# FarmControl.net
KiCad netlist of a schematic drawn in EAGLE
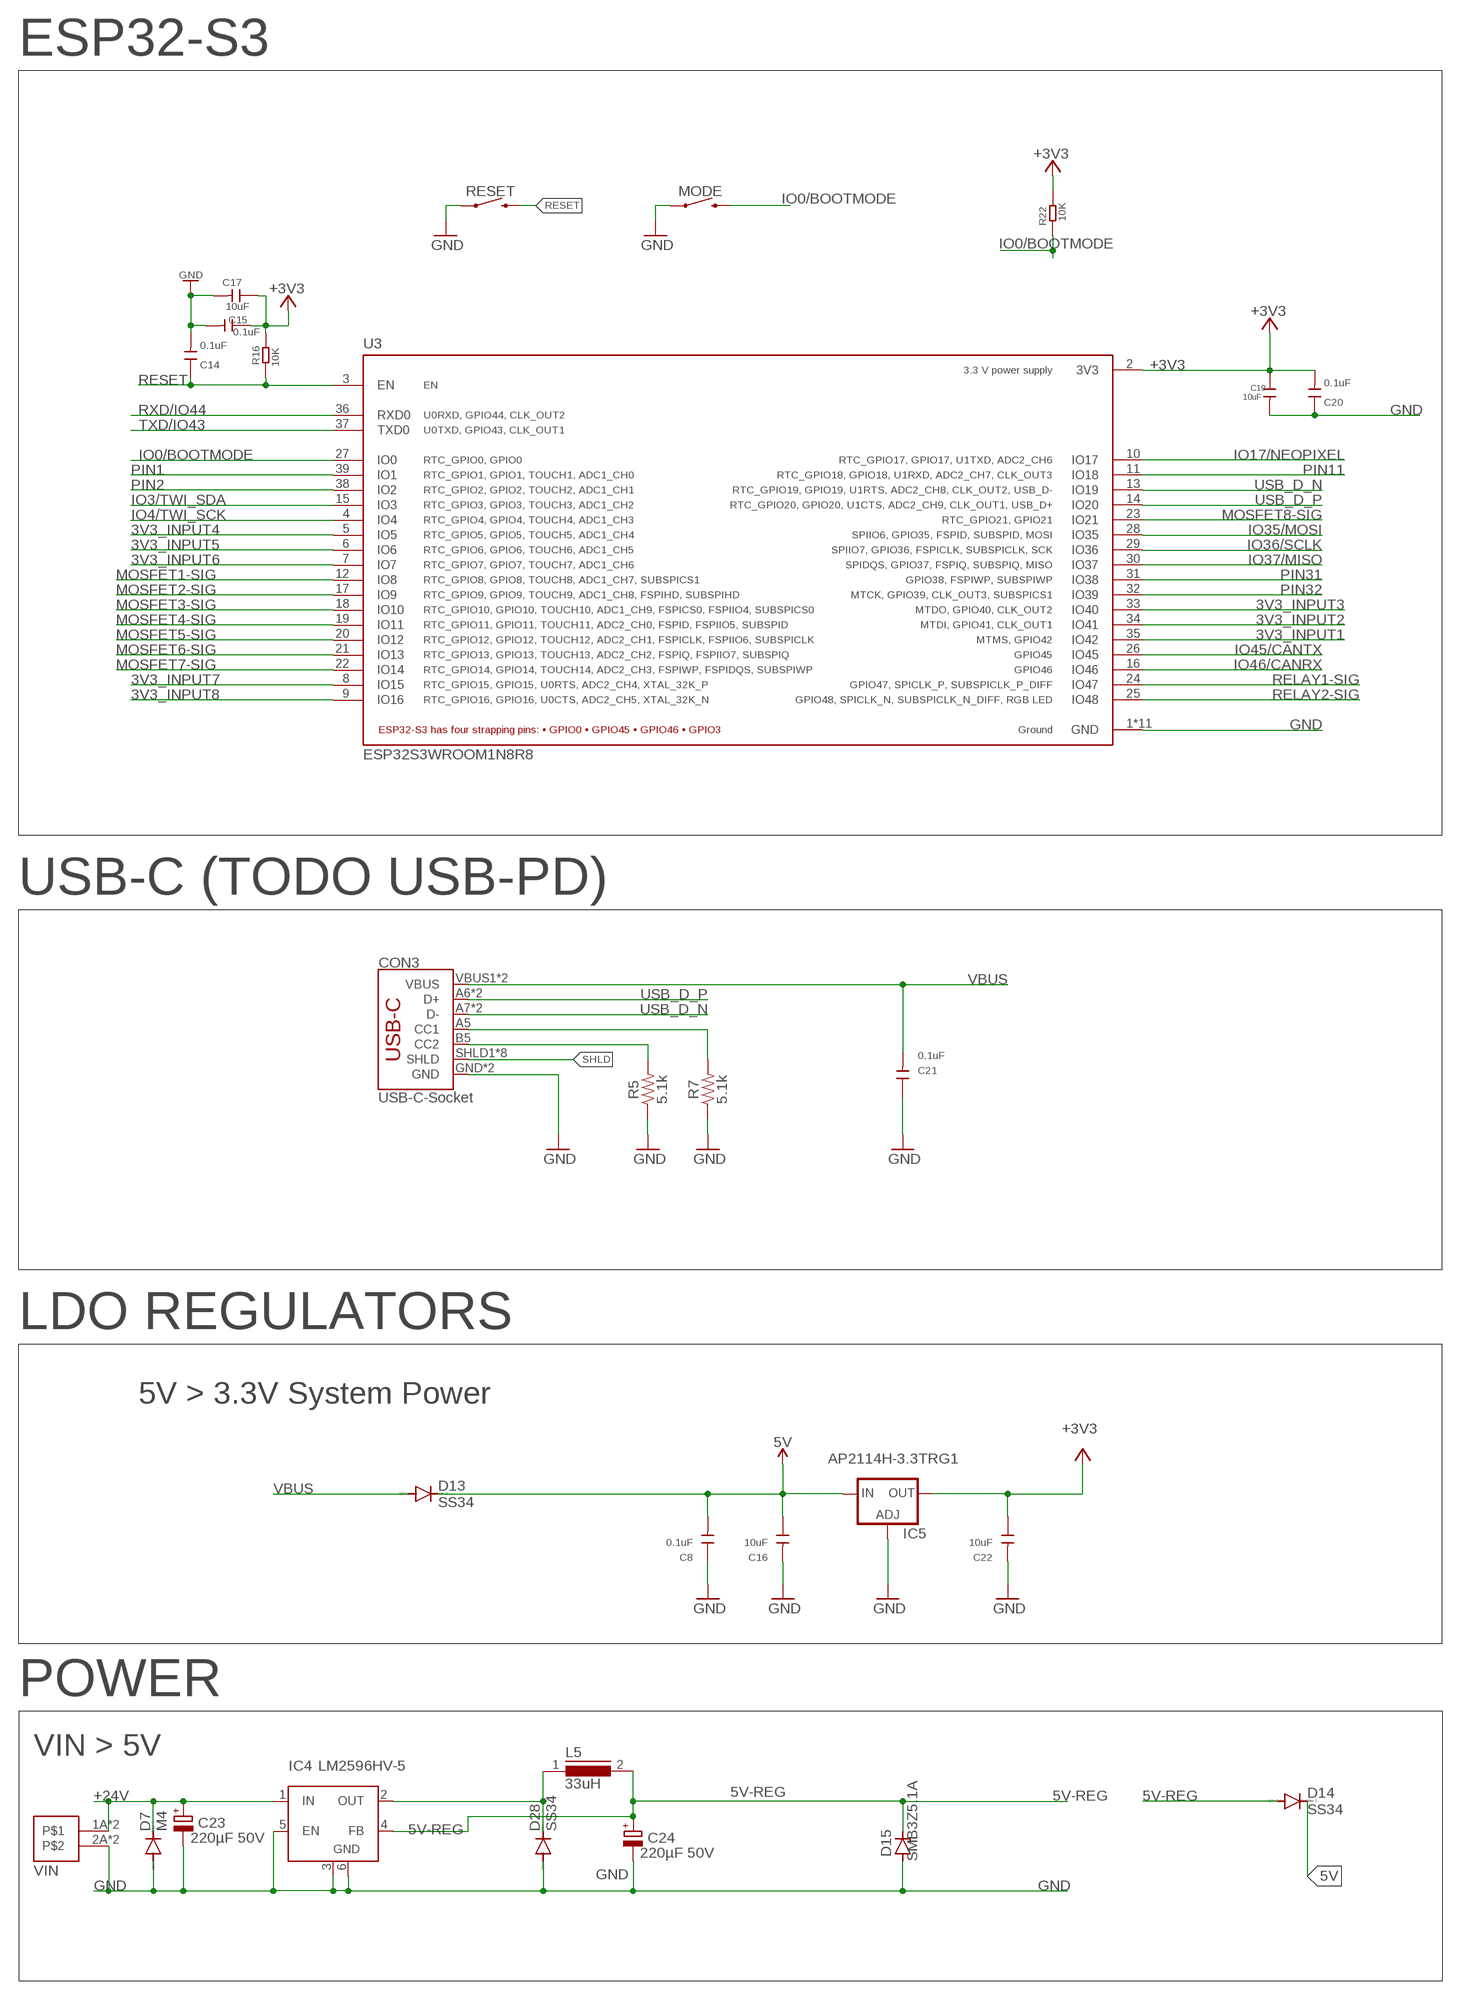
[diagram p0: schematic, sheet 1, part 1 of 3]
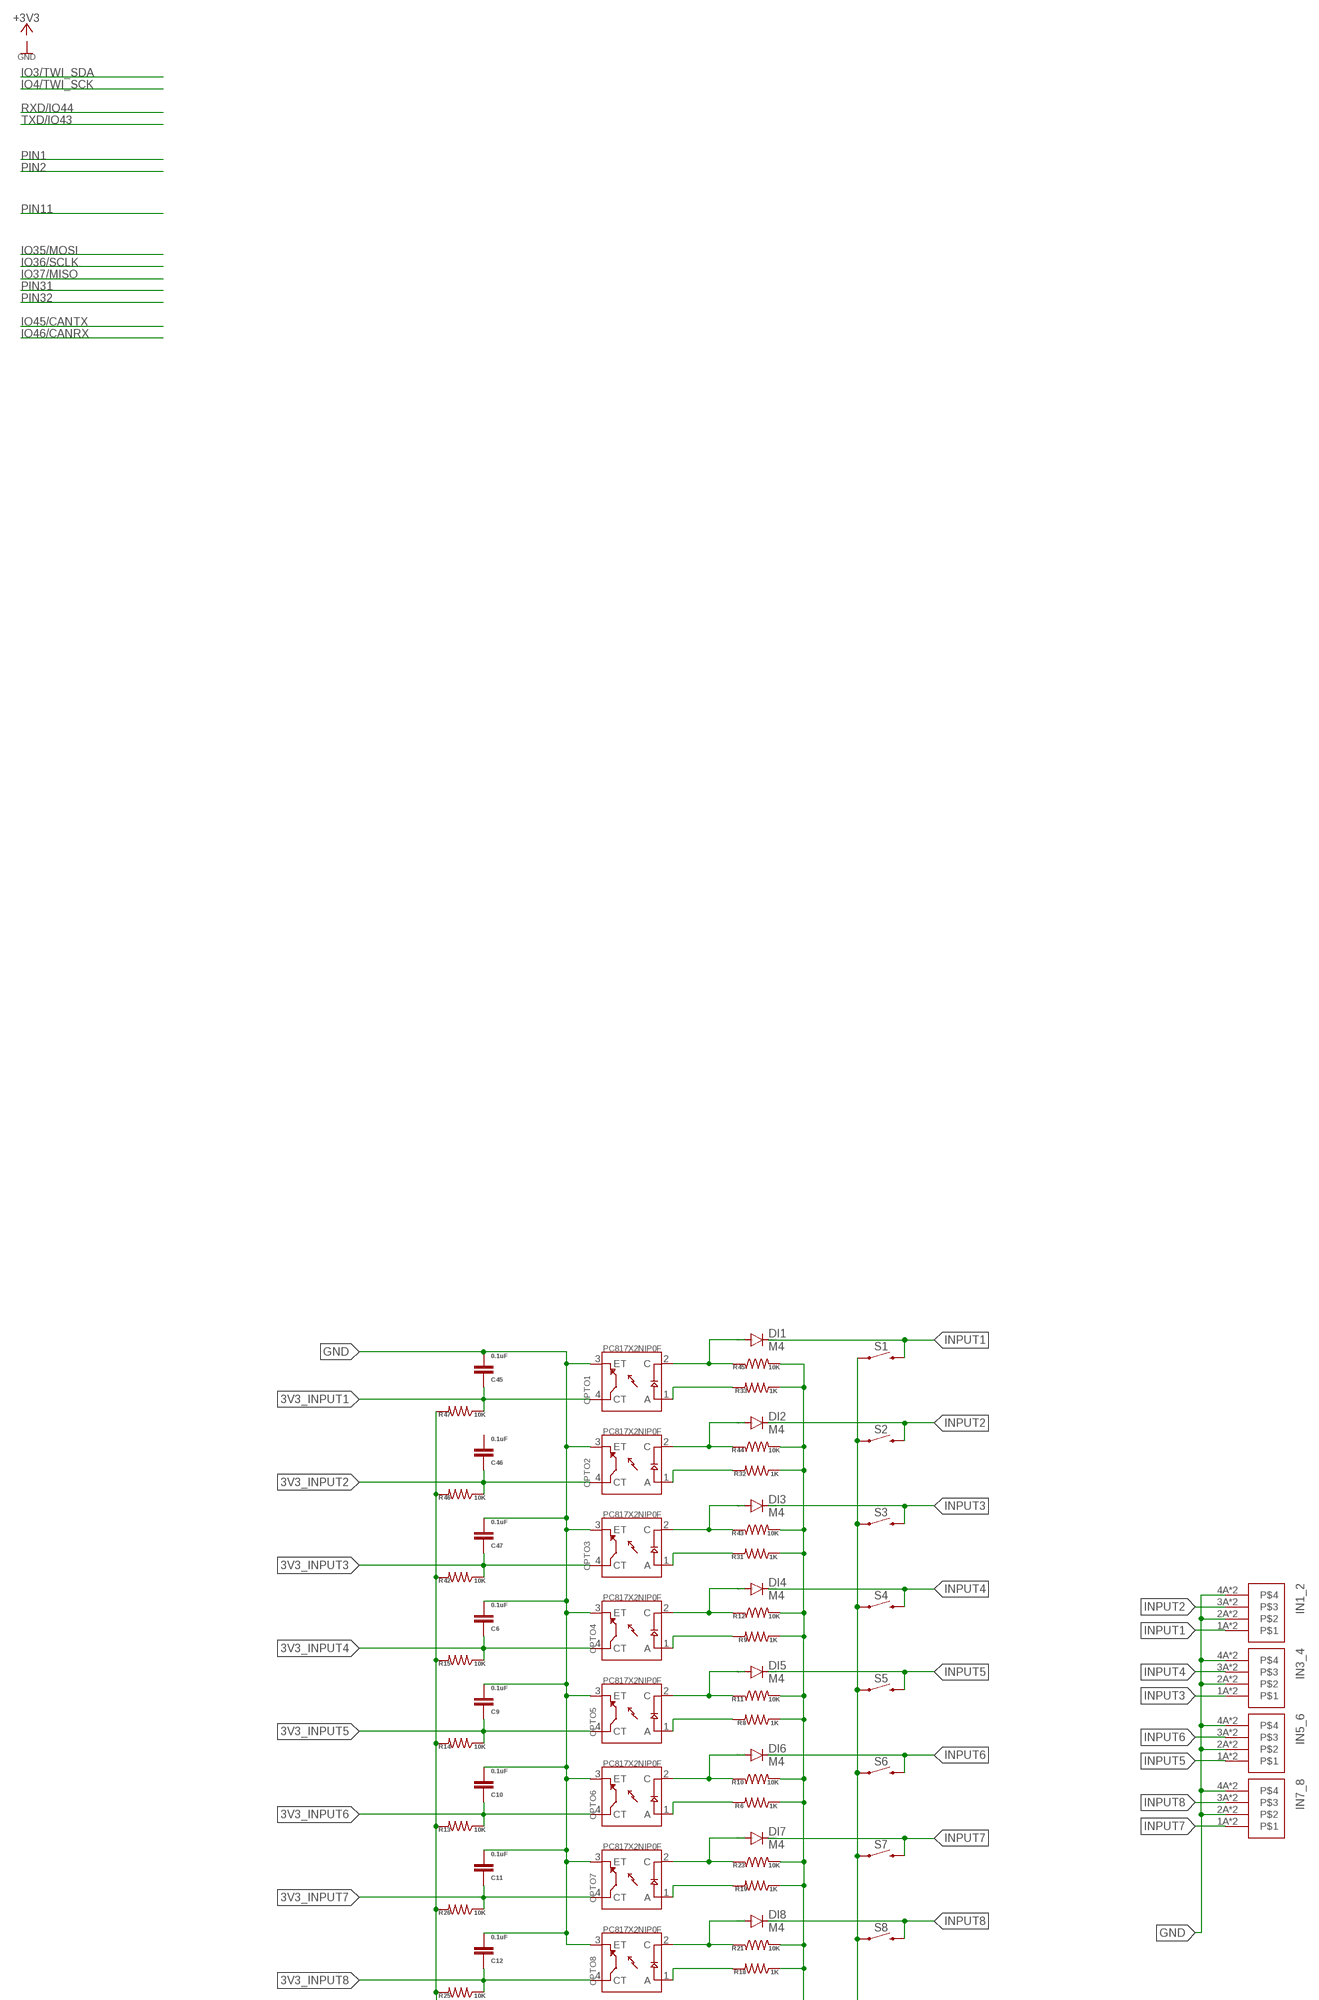
[diagram p1: schematic, sheet 1, part 2 of 3]
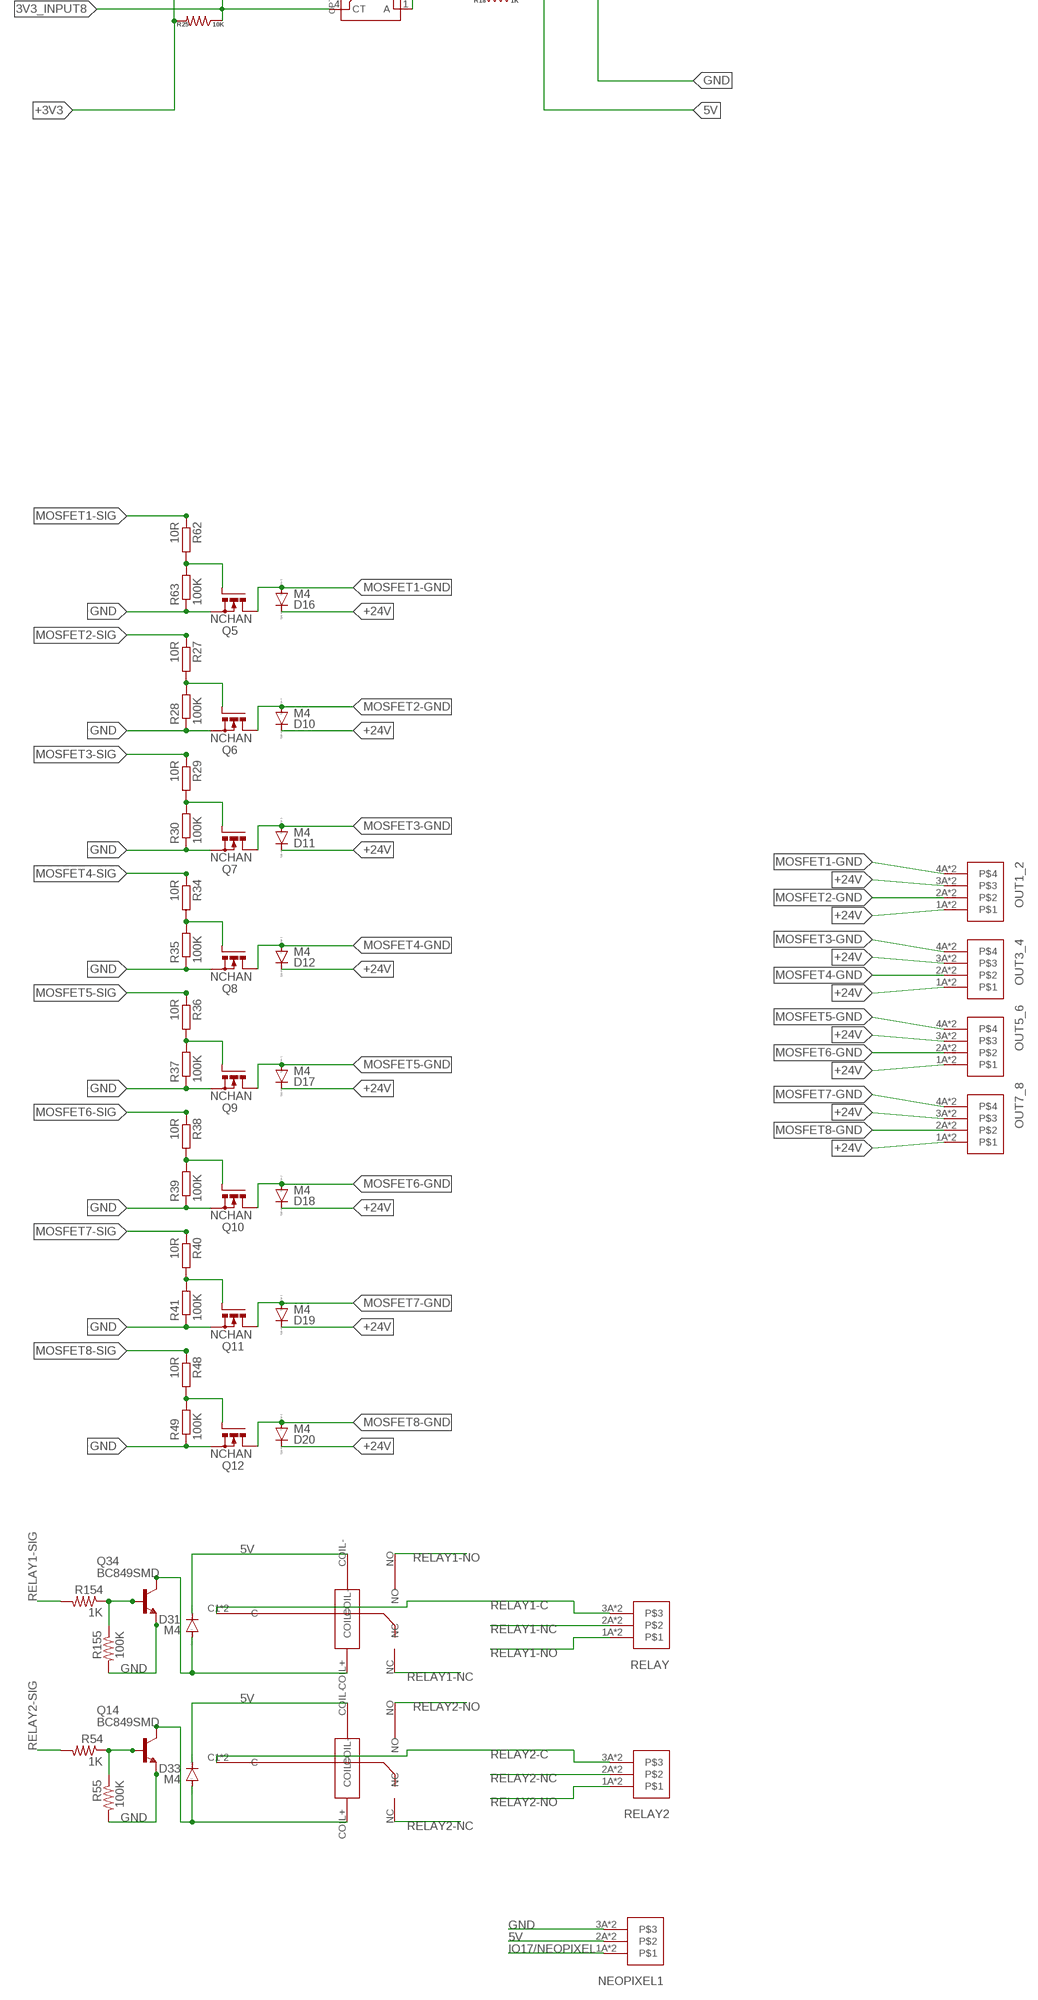
[diagram p2: schematic, sheet 1, part 3 of 3]

(export (version "E")
  (design (tool "Eeschema 10.0.6"))
  (components
    (comp (ref "C6")
      (value "0.1uF")
      (footprint "eagle-import:C1206")
      (libsource (lib "eagle-import") (part "C-EUC1206"))
    )
    (comp (ref "C8")
      (value "0.1uF")
      (footprint "eagle-import:DISCRETE_C1206")
      (libsource (lib "eagle-import") (part "DISCRETE_C-1206"))
    )
    (comp (ref "C9")
      (value "0.1uF")
      (footprint "eagle-import:C1206")
      (libsource (lib "eagle-import") (part "C-EUC1206"))
    )
    (comp (ref "C10")
      (value "0.1uF")
      (footprint "eagle-import:C1206")
      (libsource (lib "eagle-import") (part "C-EUC1206"))
    )
    (comp (ref "C11")
      (value "0.1uF")
      (footprint "eagle-import:C1206")
      (libsource (lib "eagle-import") (part "C-EUC1206"))
    )
    (comp (ref "C12")
      (value "0.1uF")
      (footprint "eagle-import:C1206")
      (libsource (lib "eagle-import") (part "C-EUC1206"))
    )
    (comp (ref "C14")
      (value "0.1uF")
      (footprint "eagle-import:DISCRETE_C1206")
      (libsource (lib "eagle-import") (part "DISCRETE_C-1206"))
    )
    (comp (ref "C15")
      (value "0.1uF")
      (footprint "eagle-import:DISCRETE_C1206")
      (libsource (lib "eagle-import") (part "DISCRETE_C-1206"))
    )
    (comp (ref "C16")
      (value "10uF")
      (footprint "eagle-import:C1206")
      (libsource (lib "eagle-import") (part "C-1206"))
    )
    (comp (ref "C17")
      (value "10uF")
      (footprint "eagle-import:DISCRETE_C1206")
      (libsource (lib "eagle-import") (part "DISCRETE_C-1206"))
    )
    (comp (ref "C19")
      (value "10uF")
      (footprint "eagle-import:C1206")
      (libsource (lib "eagle-import") (part "C-1206"))
    )
    (comp (ref "C20")
      (value "0.1uF")
      (footprint "eagle-import:DISCRETE_C1206")
      (libsource (lib "eagle-import") (part "DISCRETE_C-1206"))
    )
    (comp (ref "C21")
      (value "0.1uF")
      (footprint "eagle-import:DISCRETE_C1206")
      (libsource (lib "eagle-import") (part "DISCRETE_C-1206"))
    )
    (comp (ref "C22")
      (value "10uF")
      (footprint "eagle-import:C1206")
      (libsource (lib "eagle-import") (part "C-1206"))
    )
    (comp (ref "C23")
      (value "220µF 50V")
      (footprint "eagle-import:PANASONIC_E")
      (libsource (lib "eagle-import") (part "CPOL-EUE"))
    )
    (comp (ref "C24")
      (value "220µF 50V")
      (footprint "eagle-import:PANASONIC_E")
      (libsource (lib "eagle-import") (part "CPOL-EUE"))
    )
    (comp (ref "C45")
      (value "0.1uF")
      (footprint "eagle-import:C1206")
      (libsource (lib "eagle-import") (part "C-EUC1206"))
    )
    (comp (ref "C46")
      (value "0.1uF")
      (footprint "eagle-import:C1206")
      (libsource (lib "eagle-import") (part "C-EUC1206"))
    )
    (comp (ref "C47")
      (value "0.1uF")
      (footprint "eagle-import:C1206")
      (libsource (lib "eagle-import") (part "C-EUC1206"))
    )
    (comp (ref "CON3")
      (value "USB-C-Socket")
      (footprint "eagle-import:USB-C-16P")
      (libsource (lib "eagle-import") (part "USB_C16PIN"))
    )
    (comp (ref "D7")
      (value "M4")
      (footprint "eagle-import:DO-214AC")
      (libsource (lib "eagle-import") (part "DIODE-DO-214AC"))
    )
    (comp (ref "D10")
      (value "M4")
      (footprint "eagle-import:DO-214AC")
      (libsource (lib "eagle-import") (part "DIODE-DO-214AC"))
    )
    (comp (ref "D11")
      (value "M4")
      (footprint "eagle-import:DO-214AC")
      (libsource (lib "eagle-import") (part "DIODE-DO-214AC"))
    )
    (comp (ref "D12")
      (value "M4")
      (footprint "eagle-import:DO-214AC")
      (libsource (lib "eagle-import") (part "DIODE-DO-214AC"))
    )
    (comp (ref "D13")
      (value "SS34")
      (footprint "eagle-import:DO-214AC")
      (libsource (lib "eagle-import") (part "DIODE-DO-214AC"))
    )
    (comp (ref "D14")
      (value "SS34")
      (footprint "eagle-import:SMB")
      (libsource (lib "eagle-import") (part "DIODE-SMB"))
    )
    (comp (ref "D15")
      (value "SMB3Z5.1A")
      (footprint "eagle-import:SMB")
      (libsource (lib "eagle-import") (part "ZENER-DIODESMB"))
    )
    (comp (ref "D16")
      (value "M4")
      (footprint "eagle-import:DO-214AC")
      (libsource (lib "eagle-import") (part "DIODE-DO-214AC"))
    )
    (comp (ref "D17")
      (value "M4")
      (footprint "eagle-import:DO-214AC")
      (libsource (lib "eagle-import") (part "DIODE-DO-214AC"))
    )
    (comp (ref "D18")
      (value "M4")
      (footprint "eagle-import:DO-214AC")
      (libsource (lib "eagle-import") (part "DIODE-DO-214AC"))
    )
    (comp (ref "D19")
      (value "M4")
      (footprint "eagle-import:DO-214AC")
      (libsource (lib "eagle-import") (part "DIODE-DO-214AC"))
    )
    (comp (ref "D20")
      (value "M4")
      (footprint "eagle-import:DO-214AC")
      (libsource (lib "eagle-import") (part "DIODE-DO-214AC"))
    )
    (comp (ref "D28")
      (value "SS34")
      (footprint "eagle-import:SMB")
      (libsource (lib "eagle-import") (part "DIODE-SMB"))
    )
    (comp (ref "D31")
      (value "M4")
      (footprint "eagle-import:DO-214AC")
      (libsource (lib "eagle-import") (part "DIODE-DO-214AC"))
    )
    (comp (ref "D33")
      (value "M4")
      (footprint "eagle-import:DO-214AC")
      (libsource (lib "eagle-import") (part "DIODE-DO-214AC"))
    )
    (comp (ref "DI1")
      (value "M4")
      (footprint "eagle-import:DO-214AC")
      (libsource (lib "eagle-import") (part "DIODE-DO-214AC"))
    )
    (comp (ref "DI2")
      (value "M4")
      (footprint "eagle-import:DO-214AC")
      (libsource (lib "eagle-import") (part "DIODE-DO-214AC"))
    )
    (comp (ref "DI3")
      (value "M4")
      (footprint "eagle-import:DO-214AC")
      (libsource (lib "eagle-import") (part "DIODE-DO-214AC"))
    )
    (comp (ref "DI4")
      (value "M4")
      (footprint "eagle-import:DO-214AC")
      (libsource (lib "eagle-import") (part "DIODE-DO-214AC"))
    )
    (comp (ref "DI5")
      (value "M4")
      (footprint "eagle-import:DO-214AC")
      (libsource (lib "eagle-import") (part "DIODE-DO-214AC"))
    )
    (comp (ref "DI6")
      (value "M4")
      (footprint "eagle-import:DO-214AC")
      (libsource (lib "eagle-import") (part "DIODE-DO-214AC"))
    )
    (comp (ref "DI7")
      (value "M4")
      (footprint "eagle-import:DO-214AC")
      (libsource (lib "eagle-import") (part "DIODE-DO-214AC"))
    )
    (comp (ref "DI8")
      (value "M4")
      (footprint "eagle-import:DO-214AC")
      (libsource (lib "eagle-import") (part "DIODE-DO-214AC"))
    )
    (comp (ref "IC4")
      (value "LM2596HV-5")
      (footprint "eagle-import:TO263-5")
      (libsource (lib "eagle-import") (part "LM2596S"))
    )
    (comp (ref "IC5")
      (value "AP2114H-3.3TRG1")
      (footprint "eagle-import:SOT223")
      (libsource (lib "eagle-import") (part "LD117A?S33TR"))
    )
    (comp (ref "IN1_2")
      (value "WJ212R-THR-3.5-4")
      (footprint "eagle-import:WJ212R-THR-3.5-4")
      (libsource (lib "eagle-import") (part "WJ212R-THR-3.5-4"))
    )
    (comp (ref "IN3_4")
      (value "WJ212R-THR-3.5-4")
      (footprint "eagle-import:WJ212R-THR-3.5-4")
      (libsource (lib "eagle-import") (part "WJ212R-THR-3.5-4"))
    )
    (comp (ref "IN5_6")
      (value "WJ212R-THR-3.5-4")
      (footprint "eagle-import:WJ212R-THR-3.5-4")
      (libsource (lib "eagle-import") (part "WJ212R-THR-3.5-4"))
    )
    (comp (ref "IN7_8")
      (value "WJ212R-THR-3.5-4")
      (footprint "eagle-import:WJ212R-THR-3.5-4")
      (libsource (lib "eagle-import") (part "WJ212R-THR-3.5-4"))
    )
    (comp (ref "L5")
      (value "33uH")
      (footprint "eagle-import:DR127")
      (libsource (lib "eagle-import") (part "DR127"))
    )
    (comp (ref "MODE")
      (value "MOMENTARY-SWITCH-SPST-PTH-6.0MM")
      (footprint "eagle-import:TACTILE_SWITCH_PTH_6.0MM")
      (libsource (lib "eagle-import") (part "MOMENTARY-SWITCH-SPST-PTH-6.0MM"))
    )
    (comp (ref "NEOPIXEL1")
      (value "WJ212R-THR-3.5-3")
      (footprint "eagle-import:WJ212R-THR-3.5-3")
      (libsource (lib "eagle-import") (part "WJ212R-THR-3.5-3"))
    )
    (comp (ref "OPTO1")
      (value "PC817X2NIP0F")
      (footprint "eagle-import:SOT254P975X400-4N")
      (fields (field (name "MF") "Sharp Microelectronics"))
      (libsource (lib "eagle-import") (part "PC817X2NIP0F"))
    )
    (comp (ref "OPTO2")
      (value "PC817X2NIP0F")
      (footprint "eagle-import:SOT254P975X400-4N")
      (fields (field (name "MF") "Sharp Microelectronics"))
      (libsource (lib "eagle-import") (part "PC817X2NIP0F"))
    )
    (comp (ref "OPTO3")
      (value "PC817X2NIP0F")
      (footprint "eagle-import:SOT254P975X400-4N")
      (fields (field (name "MF") "Sharp Microelectronics"))
      (libsource (lib "eagle-import") (part "PC817X2NIP0F"))
    )
    (comp (ref "OPTO4")
      (value "PC817X2NIP0F")
      (footprint "eagle-import:SOT254P975X400-4N")
      (fields (field (name "MF") "Sharp Microelectronics"))
      (libsource (lib "eagle-import") (part "PC817X2NIP0F"))
    )
    (comp (ref "OPTO5")
      (value "PC817X2NIP0F")
      (footprint "eagle-import:SOT254P975X400-4N")
      (fields (field (name "MF") "Sharp Microelectronics"))
      (libsource (lib "eagle-import") (part "PC817X2NIP0F"))
    )
    (comp (ref "OPTO6")
      (value "PC817X2NIP0F")
      (footprint "eagle-import:SOT254P975X400-4N")
      (fields (field (name "MF") "Sharp Microelectronics"))
      (libsource (lib "eagle-import") (part "PC817X2NIP0F"))
    )
    (comp (ref "OPTO7")
      (value "PC817X2NIP0F")
      (footprint "eagle-import:SOT254P975X400-4N")
      (fields (field (name "MF") "Sharp Microelectronics"))
      (libsource (lib "eagle-import") (part "PC817X2NIP0F"))
    )
    (comp (ref "OPTO8")
      (value "PC817X2NIP0F")
      (footprint "eagle-import:SOT254P975X400-4N")
      (fields (field (name "MF") "Sharp Microelectronics"))
      (libsource (lib "eagle-import") (part "PC817X2NIP0F"))
    )
    (comp (ref "OUT1_2")
      (value "WJ212R-THR-3.5-4")
      (footprint "eagle-import:WJ212R-THR-3.5-4")
      (libsource (lib "eagle-import") (part "WJ212R-THR-3.5-4"))
    )
    (comp (ref "OUT3_4")
      (value "WJ212R-THR-3.5-4")
      (footprint "eagle-import:WJ212R-THR-3.5-4")
      (libsource (lib "eagle-import") (part "WJ212R-THR-3.5-4"))
    )
    (comp (ref "OUT5_6")
      (value "WJ212R-THR-3.5-4")
      (footprint "eagle-import:WJ212R-THR-3.5-4")
      (libsource (lib "eagle-import") (part "WJ212R-THR-3.5-4"))
    )
    (comp (ref "OUT7_8")
      (value "WJ212R-THR-3.5-4")
      (footprint "eagle-import:WJ212R-THR-3.5-4")
      (libsource (lib "eagle-import") (part "WJ212R-THR-3.5-4"))
    )
    (comp (ref "Q5")
      (value "NCHAN")
      (footprint "eagle-import:D-PAK_TO252AA")
      (libsource (lib "eagle-import") (part "N-POWER-MOSFETDPAK-MOSFET"))
    )
    (comp (ref "Q6")
      (value "NCHAN")
      (footprint "eagle-import:D-PAK_TO252AA")
      (libsource (lib "eagle-import") (part "N-POWER-MOSFETDPAK-MOSFET"))
    )
    (comp (ref "Q7")
      (value "NCHAN")
      (footprint "eagle-import:D-PAK_TO252AA")
      (libsource (lib "eagle-import") (part "N-POWER-MOSFETDPAK-MOSFET"))
    )
    (comp (ref "Q8")
      (value "NCHAN")
      (footprint "eagle-import:D-PAK_TO252AA")
      (libsource (lib "eagle-import") (part "N-POWER-MOSFETDPAK-MOSFET"))
    )
    (comp (ref "Q9")
      (value "NCHAN")
      (footprint "eagle-import:D-PAK_TO252AA")
      (libsource (lib "eagle-import") (part "N-POWER-MOSFETDPAK-MOSFET"))
    )
    (comp (ref "Q10")
      (value "NCHAN")
      (footprint "eagle-import:D-PAK_TO252AA")
      (libsource (lib "eagle-import") (part "N-POWER-MOSFETDPAK-MOSFET"))
    )
    (comp (ref "Q11")
      (value "NCHAN")
      (footprint "eagle-import:D-PAK_TO252AA")
      (libsource (lib "eagle-import") (part "N-POWER-MOSFETDPAK-MOSFET"))
    )
    (comp (ref "Q12")
      (value "NCHAN")
      (footprint "eagle-import:D-PAK_TO252AA")
      (libsource (lib "eagle-import") (part "N-POWER-MOSFETDPAK-MOSFET"))
    )
    (comp (ref "Q14")
      (value "BC849SMD")
      (footprint "eagle-import:SOT23-BEC")
      (libsource (lib "eagle-import") (part "BC849SMD"))
    )
    (comp (ref "Q34")
      (value "BC849SMD")
      (footprint "eagle-import:SOT23-BEC")
      (libsource (lib "eagle-import") (part "BC849SMD"))
    )
    (comp (ref "R5")
      (value "5.1k")
      (footprint "eagle-import:0603@1")
      (libsource (lib "eagle-import") (part "5.1KOHM5.1KOHM-0603-1/10W-1%"))
    )
    (comp (ref "R6")
      (value "1K")
      (footprint "eagle-import:R1206")
      (libsource (lib "eagle-import") (part "resistor_R-US_R1206"))
    )
    (comp (ref "R7")
      (value "5.1k")
      (footprint "eagle-import:0603@1")
      (libsource (lib "eagle-import") (part "5.1KOHM5.1KOHM-0603-1/10W-1%"))
    )
    (comp (ref "R8")
      (value "1K")
      (footprint "eagle-import:R1206")
      (libsource (lib "eagle-import") (part "resistor_R-US_R1206"))
    )
    (comp (ref "R9")
      (value "1K")
      (footprint "eagle-import:R1206")
      (libsource (lib "eagle-import") (part "resistor_R-US_R1206"))
    )
    (comp (ref "R10")
      (value "10K")
      (footprint "eagle-import:R1206")
      (libsource (lib "eagle-import") (part "resistor_R-US_R1206"))
    )
    (comp (ref "R11")
      (value "10K")
      (footprint "eagle-import:R1206")
      (libsource (lib "eagle-import") (part "resistor_R-US_R1206"))
    )
    (comp (ref "R12")
      (value "10K")
      (footprint "eagle-import:R1206")
      (libsource (lib "eagle-import") (part "resistor_R-US_R1206"))
    )
    (comp (ref "R13")
      (value "10K")
      (footprint "eagle-import:R1206")
      (libsource (lib "eagle-import") (part "resistor_R-US_R1206"))
    )
    (comp (ref "R14")
      (value "10K")
      (footprint "eagle-import:R1206")
      (libsource (lib "eagle-import") (part "resistor_R-US_R1206"))
    )
    (comp (ref "R15")
      (value "10K")
      (footprint "eagle-import:R1206")
      (libsource (lib "eagle-import") (part "resistor_R-US_R1206"))
    )
    (comp (ref "R16")
      (value "10K")
      (footprint "eagle-import:R1206")
      (libsource (lib "eagle-import") (part "R-1206"))
    )
    (comp (ref "R18")
      (value "1K")
      (footprint "eagle-import:R1206")
      (libsource (lib "eagle-import") (part "resistor_R-US_R1206"))
    )
    (comp (ref "R19")
      (value "1K")
      (footprint "eagle-import:R1206")
      (libsource (lib "eagle-import") (part "resistor_R-US_R1206"))
    )
    (comp (ref "R21")
      (value "10K")
      (footprint "eagle-import:R1206")
      (libsource (lib "eagle-import") (part "resistor_R-US_R1206"))
    )
    (comp (ref "R22")
      (value "10K")
      (footprint "eagle-import:R1206")
      (libsource (lib "eagle-import") (part "R-1206"))
    )
    (comp (ref "R23")
      (value "10K")
      (footprint "eagle-import:R1206")
      (libsource (lib "eagle-import") (part "resistor_R-US_R1206"))
    )
    (comp (ref "R25")
      (value "10K")
      (footprint "eagle-import:R1206")
      (libsource (lib "eagle-import") (part "resistor_R-US_R1206"))
    )
    (comp (ref "R26")
      (value "10K")
      (footprint "eagle-import:R1206")
      (libsource (lib "eagle-import") (part "resistor_R-US_R1206"))
    )
    (comp (ref "R27")
      (value "10R")
      (footprint "eagle-import:R1206")
      (libsource (lib "eagle-import") (part "R-EU_R1206"))
    )
    (comp (ref "R28")
      (value "100K")
      (footprint "eagle-import:R1206")
      (libsource (lib "eagle-import") (part "R-EU_R1206"))
    )
    (comp (ref "R29")
      (value "10R")
      (footprint "eagle-import:R1206")
      (libsource (lib "eagle-import") (part "R-EU_R1206"))
    )
    (comp (ref "R30")
      (value "100K")
      (footprint "eagle-import:R1206")
      (libsource (lib "eagle-import") (part "R-EU_R1206"))
    )
    (comp (ref "R31")
      (value "1K")
      (footprint "eagle-import:R1206")
      (libsource (lib "eagle-import") (part "resistor_R-US_R1206"))
    )
    (comp (ref "R32")
      (value "1K")
      (footprint "eagle-import:R1206")
      (libsource (lib "eagle-import") (part "resistor_R-US_R1206"))
    )
    (comp (ref "R33")
      (value "1K")
      (footprint "eagle-import:R1206")
      (libsource (lib "eagle-import") (part "resistor_R-US_R1206"))
    )
    (comp (ref "R34")
      (value "10R")
      (footprint "eagle-import:R1206")
      (libsource (lib "eagle-import") (part "R-EU_R1206"))
    )
    (comp (ref "R35")
      (value "100K")
      (footprint "eagle-import:R1206")
      (libsource (lib "eagle-import") (part "R-EU_R1206"))
    )
    (comp (ref "R36")
      (value "10R")
      (footprint "eagle-import:R1206")
      (libsource (lib "eagle-import") (part "R-EU_R1206"))
    )
    (comp (ref "R37")
      (value "100K")
      (footprint "eagle-import:R1206")
      (libsource (lib "eagle-import") (part "R-EU_R1206"))
    )
    (comp (ref "R38")
      (value "10R")
      (footprint "eagle-import:R1206")
      (libsource (lib "eagle-import") (part "R-EU_R1206"))
    )
    (comp (ref "R39")
      (value "100K")
      (footprint "eagle-import:R1206")
      (libsource (lib "eagle-import") (part "R-EU_R1206"))
    )
    (comp (ref "R40")
      (value "10R")
      (footprint "eagle-import:R1206")
      (libsource (lib "eagle-import") (part "R-EU_R1206"))
    )
    (comp (ref "R41")
      (value "100K")
      (footprint "eagle-import:R1206")
      (libsource (lib "eagle-import") (part "R-EU_R1206"))
    )
    (comp (ref "R42")
      (value "10K")
      (footprint "eagle-import:R1206")
      (libsource (lib "eagle-import") (part "resistor_R-US_R1206"))
    )
    (comp (ref "R43")
      (value "10K")
      (footprint "eagle-import:R1206")
      (libsource (lib "eagle-import") (part "resistor_R-US_R1206"))
    )
    (comp (ref "R44")
      (value "10K")
      (footprint "eagle-import:R1206")
      (libsource (lib "eagle-import") (part "resistor_R-US_R1206"))
    )
    (comp (ref "R45")
      (value "10K")
      (footprint "eagle-import:R1206")
      (libsource (lib "eagle-import") (part "resistor_R-US_R1206"))
    )
    (comp (ref "R46")
      (value "10K")
      (footprint "eagle-import:R1206")
      (libsource (lib "eagle-import") (part "resistor_R-US_R1206"))
    )
    (comp (ref "R47")
      (value "10K")
      (footprint "eagle-import:R1206")
      (libsource (lib "eagle-import") (part "resistor_R-US_R1206"))
    )
    (comp (ref "R48")
      (value "10R")
      (footprint "eagle-import:R1206")
      (libsource (lib "eagle-import") (part "R-EU_R1206"))
    )
    (comp (ref "R49")
      (value "100K")
      (footprint "eagle-import:R1206")
      (libsource (lib "eagle-import") (part "R-EU_R1206"))
    )
    (comp (ref "R54")
      (value "1K")
      (footprint "eagle-import:R1206")
      (libsource (lib "eagle-import") (part "R-US_R1206"))
    )
    (comp (ref "R55")
      (value "100K")
      (footprint "eagle-import:R1206")
      (libsource (lib "eagle-import") (part "R-US_R1206"))
    )
    (comp (ref "R62")
      (value "10R")
      (footprint "eagle-import:R1206")
      (libsource (lib "eagle-import") (part "R-EU_R1206"))
    )
    (comp (ref "R63")
      (value "100K")
      (footprint "eagle-import:R1206")
      (libsource (lib "eagle-import") (part "R-EU_R1206"))
    )
    (comp (ref "R154")
      (value "1K")
      (footprint "eagle-import:R1206")
      (libsource (lib "eagle-import") (part "R-US_R1206"))
    )
    (comp (ref "R155")
      (value "100K")
      (footprint "eagle-import:R1206")
      (libsource (lib "eagle-import") (part "R-US_R1206"))
    )
    (comp (ref "RELAY")
      (value "WJ212R-THR-3.5-3")
      (footprint "eagle-import:WJ212R-THR-3.5-3")
      (libsource (lib "eagle-import") (part "WJ212R-THR-3.5-3"))
    )
    (comp (ref "RELAY2")
      (value "WJ212R-THR-3.5-3")
      (footprint "eagle-import:WJ212R-THR-3.5-3")
      (libsource (lib "eagle-import") (part "WJ212R-THR-3.5-3"))
    )
    (comp (ref "RESET")
      (value "MOMENTARY-SWITCH-SPST-PTH-6.0MM")
      (footprint "eagle-import:TACTILE_SWITCH_PTH_6.0MM")
      (libsource (lib "eagle-import") (part "MOMENTARY-SWITCH-SPST-PTH-6.0MM"))
    )
    (comp (ref "S1")
      (value "MOMENTARY-SWITCH-SPST-PTH-6.0MM")
      (footprint "eagle-import:TACTILE_SWITCH_PTH_6.0MM")
      (libsource (lib "eagle-import") (part "MOMENTARY-SWITCH-SPST-PTH-6.0MM"))
    )
    (comp (ref "S2")
      (value "MOMENTARY-SWITCH-SPST-PTH-6.0MM")
      (footprint "eagle-import:TACTILE_SWITCH_PTH_6.0MM")
      (libsource (lib "eagle-import") (part "MOMENTARY-SWITCH-SPST-PTH-6.0MM"))
    )
    (comp (ref "S3")
      (value "MOMENTARY-SWITCH-SPST-PTH-6.0MM")
      (footprint "eagle-import:TACTILE_SWITCH_PTH_6.0MM")
      (libsource (lib "eagle-import") (part "MOMENTARY-SWITCH-SPST-PTH-6.0MM"))
    )
    (comp (ref "S4")
      (value "MOMENTARY-SWITCH-SPST-PTH-6.0MM")
      (footprint "eagle-import:TACTILE_SWITCH_PTH_6.0MM")
      (libsource (lib "eagle-import") (part "MOMENTARY-SWITCH-SPST-PTH-6.0MM"))
    )
    (comp (ref "S5")
      (value "MOMENTARY-SWITCH-SPST-PTH-6.0MM")
      (footprint "eagle-import:TACTILE_SWITCH_PTH_6.0MM")
      (libsource (lib "eagle-import") (part "MOMENTARY-SWITCH-SPST-PTH-6.0MM"))
    )
    (comp (ref "S6")
      (value "MOMENTARY-SWITCH-SPST-PTH-6.0MM")
      (footprint "eagle-import:TACTILE_SWITCH_PTH_6.0MM")
      (libsource (lib "eagle-import") (part "MOMENTARY-SWITCH-SPST-PTH-6.0MM"))
    )
    (comp (ref "S7")
      (value "MOMENTARY-SWITCH-SPST-PTH-6.0MM")
      (footprint "eagle-import:TACTILE_SWITCH_PTH_6.0MM")
      (libsource (lib "eagle-import") (part "MOMENTARY-SWITCH-SPST-PTH-6.0MM"))
    )
    (comp (ref "S8")
      (value "MOMENTARY-SWITCH-SPST-PTH-6.0MM")
      (footprint "eagle-import:TACTILE_SWITCH_PTH_6.0MM")
      (libsource (lib "eagle-import") (part "MOMENTARY-SWITCH-SPST-PTH-6.0MM"))
    )
    (comp (ref "U$1")
      (value "JRC-21F-4100")
      (footprint "eagle-import:JRC-21F-4100")
      (libsource (lib "eagle-import") (part "JRC-21F-4100"))
    )
    (comp (ref "U$3")
      (value "JRC-21F-4100")
      (footprint "eagle-import:JRC-21F-4100")
      (libsource (lib "eagle-import") (part "JRC-21F-4100"))
    )
    (comp (ref "U3")
      (value "ESP32S3WROOM1N8R8")
      (footprint "eagle-import:XCVR_ESP32S3WROOM1N8R8")
      (fields (field (name "MF") "Espressif Systems"))
      (libsource (lib "eagle-import") (part "ESP32S3WROOM1N8R8"))
    )
    (comp (ref "VIN")
      (value "WJ212R-THR-3.5-2")
      (footprint "eagle-import:WJ212R-THR-3.5-2")
      (libsource (lib "eagle-import") (part "WJ212R-THR-3.5-2"))
    )
  )
  (nets
    (net (code "1") (name "+3V3") (class "Default")
      (node (ref "C15") (pin "1") (pinfunction "1_1") (pintype "passive"))
      (node (ref "C17") (pin "1") (pinfunction "1_1") (pintype "passive"))
      (node (ref "C19") (pin "1") (pinfunction "1_1") (pintype "passive"))
      (node (ref "C20") (pin "2") (pinfunction "2_2") (pintype "passive"))
      (node (ref "C22") (pin "1") (pinfunction "1_1") (pintype "passive"))
      (node (ref "IC5") (pin "4") (pinfunction "OUT_4") (pintype "passive"))
      (node (ref "R13") (pin "2") (pinfunction "2_2") (pintype "passive"))
      (node (ref "R14") (pin "2") (pinfunction "2_2") (pintype "passive"))
      (node (ref "R15") (pin "2") (pinfunction "2_2") (pintype "passive"))
      (node (ref "R16") (pin "2") (pinfunction "2_2") (pintype "passive"))
      (node (ref "R22") (pin "2") (pinfunction "2_2") (pintype "passive"))
      (node (ref "R25") (pin "2") (pinfunction "2_2") (pintype "passive"))
      (node (ref "R26") (pin "2") (pinfunction "2_2") (pintype "passive"))
      (node (ref "R42") (pin "2") (pinfunction "2_2") (pintype "passive"))
      (node (ref "R46") (pin "2") (pinfunction "2_2") (pintype "passive"))
      (node (ref "R47") (pin "2") (pinfunction "2_2") (pintype "passive"))
      (node (ref "U3") (pin "2") (pinfunction "3V3_2") (pintype "power_in"))
    )
    (net (code "2") (name "+24V") (class "Default")
      (node (ref "C23") (pin "+") (pinfunction "+_+") (pintype "passive"))
      (node (ref "D10") (pin "C") (pinfunction "C_C") (pintype "passive"))
      (node (ref "D11") (pin "C") (pinfunction "C_C") (pintype "passive"))
      (node (ref "D12") (pin "C") (pinfunction "C_C") (pintype "passive"))
      (node (ref "D16") (pin "C") (pinfunction "C_C") (pintype "passive"))
      (node (ref "D17") (pin "C") (pinfunction "C_C") (pintype "passive"))
      (node (ref "D18") (pin "C") (pinfunction "C_C") (pintype "passive"))
      (node (ref "D19") (pin "C") (pinfunction "C_C") (pintype "passive"))
      (node (ref "D20") (pin "C") (pinfunction "C_C") (pintype "passive"))
      (node (ref "D7") (pin "C") (pinfunction "C_C") (pintype "passive"))
      (node (ref "IC4") (pin "1") (pinfunction "IN_1") (pintype "input"))
      (node (ref "OUT1_2") (pin "1A") (pinfunction "P$1_1A") (pintype "bidirectional"))
      (node (ref "OUT1_2") (pin "1B") (pinfunction "P$1_1B") (pintype "bidirectional"))
      (node (ref "OUT1_2") (pin "3A") (pinfunction "P$3_3A") (pintype "bidirectional"))
      (node (ref "OUT1_2") (pin "3B") (pinfunction "P$3_3B") (pintype "bidirectional"))
      (node (ref "OUT3_4") (pin "1A") (pinfunction "P$1_1A") (pintype "bidirectional"))
      (node (ref "OUT3_4") (pin "1B") (pinfunction "P$1_1B") (pintype "bidirectional"))
      (node (ref "OUT3_4") (pin "3A") (pinfunction "P$3_3A") (pintype "bidirectional"))
      (node (ref "OUT3_4") (pin "3B") (pinfunction "P$3_3B") (pintype "bidirectional"))
      (node (ref "OUT5_6") (pin "1A") (pinfunction "P$1_1A") (pintype "bidirectional"))
      (node (ref "OUT5_6") (pin "1B") (pinfunction "P$1_1B") (pintype "bidirectional"))
      (node (ref "OUT5_6") (pin "3A") (pinfunction "P$3_3A") (pintype "bidirectional"))
      (node (ref "OUT5_6") (pin "3B") (pinfunction "P$3_3B") (pintype "bidirectional"))
      (node (ref "OUT7_8") (pin "1A") (pinfunction "P$1_1A") (pintype "bidirectional"))
      (node (ref "OUT7_8") (pin "1B") (pinfunction "P$1_1B") (pintype "bidirectional"))
      (node (ref "OUT7_8") (pin "3A") (pinfunction "P$3_3A") (pintype "bidirectional"))
      (node (ref "OUT7_8") (pin "3B") (pinfunction "P$3_3B") (pintype "bidirectional"))
      (node (ref "VIN") (pin "1A") (pinfunction "P$1_1A") (pintype "bidirectional"))
      (node (ref "VIN") (pin "1B") (pinfunction "P$1_1B") (pintype "bidirectional"))
    )
    (net (code "3") (name "/5V-REG") (class "Default")
      (node (ref "C24") (pin "+") (pinfunction "+_+") (pintype "passive"))
      (node (ref "D14") (pin "A") (pinfunction "A_A") (pintype "passive"))
      (node (ref "D15") (pin "C") (pinfunction "C_C") (pintype "passive"))
      (node (ref "IC4") (pin "4") (pinfunction "FB_4") (pintype "input"))
      (node (ref "L5") (pin "2") (pinfunction "2_2") (pintype "passive"))
    )
    (net (code "4") (name "/IO0{slash}BOOTMODE") (class "Default")
      (node (ref "MODE") (pin "3") (pinfunction "2_3") (pintype "passive"))
      (node (ref "R22") (pin "1") (pinfunction "1_1") (pintype "passive"))
      (node (ref "U3") (pin "27") (pinfunction "IO0_27") (pintype "bidirectional"))
    )
    (net (code "5") (name "/IO3{slash}TWI_SDA") (class "Default")
      (node (ref "U3") (pin "15") (pinfunction "IO3_15") (pintype "bidirectional"))
    )
    (net (code "6") (name "/IO4{slash}TWI_SCK") (class "Default")
      (node (ref "U3") (pin "4") (pinfunction "IO4_4") (pintype "bidirectional"))
    )
    (net (code "7") (name "/IO17{slash}NEOPIXEL") (class "Default")
      (node (ref "NEOPIXEL1") (pin "1A") (pinfunction "P$1_1A") (pintype "bidirectional"))
      (node (ref "NEOPIXEL1") (pin "1B") (pinfunction "P$1_1B") (pintype "bidirectional"))
      (node (ref "U3") (pin "10") (pinfunction "IO17_10") (pintype "bidirectional"))
    )
    (net (code "8") (name "/IO35{slash}MOSI") (class "Default")
      (node (ref "U3") (pin "28") (pinfunction "IO35_28") (pintype "bidirectional"))
    )
    (net (code "9") (name "/IO36{slash}SCLK") (class "Default")
      (node (ref "U3") (pin "29") (pinfunction "IO36_29") (pintype "bidirectional"))
    )
    (net (code "10") (name "/IO37{slash}MISO") (class "Default")
      (node (ref "U3") (pin "30") (pinfunction "IO37_30") (pintype "bidirectional"))
    )
    (net (code "11") (name "/IO45{slash}CANTX") (class "Default")
      (node (ref "U3") (pin "26") (pinfunction "IO45_26") (pintype "bidirectional"))
    )
    (net (code "12") (name "/IO46{slash}CANRX") (class "Default")
      (node (ref "U3") (pin "16") (pinfunction "IO46_16") (pintype "bidirectional"))
    )
    (net (code "13") (name "/PIN1") (class "Default")
      (node (ref "U3") (pin "39") (pinfunction "IO1_39") (pintype "bidirectional"))
    )
    (net (code "14") (name "/PIN2") (class "Default")
      (node (ref "U3") (pin "38") (pinfunction "IO2_38") (pintype "bidirectional"))
    )
    (net (code "15") (name "/PIN11") (class "Default")
      (node (ref "U3") (pin "11") (pinfunction "IO18_11") (pintype "bidirectional"))
    )
    (net (code "16") (name "/PIN31") (class "Default")
      (node (ref "U3") (pin "31") (pinfunction "IO38_31") (pintype "bidirectional"))
    )
    (net (code "17") (name "/PIN32") (class "Default")
      (node (ref "U3") (pin "32") (pinfunction "IO39_32") (pintype "bidirectional"))
    )
    (net (code "18") (name "/RELAY1-C") (class "Default")
      (node (ref "RELAY") (pin "3A") (pinfunction "P$3_3A") (pintype "bidirectional"))
      (node (ref "RELAY") (pin "3B") (pinfunction "P$3_3B") (pintype "bidirectional"))
      (node (ref "U$3") (pin "C1") (pinfunction "C_C1") (pintype "bidirectional"))
      (node (ref "U$3") (pin "C2") (pinfunction "C_C2") (pintype "bidirectional"))
    )
    (net (code "19") (name "/RELAY1-NC") (class "Default")
      (node (ref "RELAY") (pin "2A") (pinfunction "P$2_2A") (pintype "bidirectional"))
      (node (ref "RELAY") (pin "2B") (pinfunction "P$2_2B") (pintype "bidirectional"))
      (node (ref "U$3") (pin "NC") (pinfunction "NC_NC") (pintype "bidirectional"))
    )
    (net (code "20") (name "/RELAY1-NO") (class "Default")
      (node (ref "RELAY") (pin "1A") (pinfunction "P$1_1A") (pintype "bidirectional"))
      (node (ref "RELAY") (pin "1B") (pinfunction "P$1_1B") (pintype "bidirectional"))
      (node (ref "U$3") (pin "NO") (pinfunction "NO_NO") (pintype "bidirectional"))
    )
    (net (code "21") (name "/RELAY1-SIG") (class "Default")
      (node (ref "R154") (pin "2") (pinfunction "2_2") (pintype "passive"))
      (node (ref "U3") (pin "24") (pinfunction "IO47_24") (pintype "bidirectional"))
    )
    (net (code "22") (name "/RELAY2-C") (class "Default")
      (node (ref "RELAY2") (pin "3A") (pinfunction "P$3_3A") (pintype "bidirectional"))
      (node (ref "RELAY2") (pin "3B") (pinfunction "P$3_3B") (pintype "bidirectional"))
      (node (ref "U$1") (pin "C1") (pinfunction "C_C1") (pintype "bidirectional"))
      (node (ref "U$1") (pin "C2") (pinfunction "C_C2") (pintype "bidirectional"))
    )
    (net (code "23") (name "/RELAY2-NC") (class "Default")
      (node (ref "RELAY2") (pin "2A") (pinfunction "P$2_2A") (pintype "bidirectional"))
      (node (ref "RELAY2") (pin "2B") (pinfunction "P$2_2B") (pintype "bidirectional"))
      (node (ref "U$1") (pin "NC") (pinfunction "NC_NC") (pintype "bidirectional"))
    )
    (net (code "24") (name "/RELAY2-NO") (class "Default")
      (node (ref "RELAY2") (pin "1A") (pinfunction "P$1_1A") (pintype "bidirectional"))
      (node (ref "RELAY2") (pin "1B") (pinfunction "P$1_1B") (pintype "bidirectional"))
      (node (ref "U$1") (pin "NO") (pinfunction "NO_NO") (pintype "bidirectional"))
    )
    (net (code "25") (name "/RELAY2-SIG") (class "Default")
      (node (ref "R54") (pin "2") (pinfunction "2_2") (pintype "passive"))
      (node (ref "U3") (pin "25") (pinfunction "IO48_25") (pintype "bidirectional"))
    )
    (net (code "26") (name "/RXD{slash}IO44") (class "Default")
      (node (ref "U3") (pin "36") (pinfunction "RXD0_36") (pintype "bidirectional"))
    )
    (net (code "27") (name "/TXD{slash}IO43") (class "Default")
      (node (ref "U3") (pin "37") (pinfunction "TXD0_37") (pintype "bidirectional"))
    )
    (net (code "28") (name "/USB_D_N") (class "Default")
      (node (ref "CON3") (pin "A7") (pinfunction "D-_A7") (pintype "bidirectional"))
      (node (ref "CON3") (pin "B7") (pinfunction "D-_B7") (pintype "bidirectional"))
      (node (ref "U3") (pin "13") (pinfunction "IO19_13") (pintype "bidirectional"))
    )
    (net (code "29") (name "/USB_D_P") (class "Default")
      (node (ref "CON3") (pin "A6") (pinfunction "D+_A6") (pintype "bidirectional"))
      (node (ref "CON3") (pin "B6") (pinfunction "D+_B6") (pintype "bidirectional"))
      (node (ref "U3") (pin "14") (pinfunction "IO20_14") (pintype "bidirectional"))
    )
    (net (code "30") (name "/VBUS") (class "Default")
      (node (ref "C21") (pin "2") (pinfunction "2_2") (pintype "passive"))
      (node (ref "CON3") (pin "VBUS1") (pinfunction "VBUS_VBUS1") (pintype "bidirectional"))
      (node (ref "CON3") (pin "VBUS2") (pinfunction "VBUS_VBUS2") (pintype "bidirectional"))
      (node (ref "D13") (pin "A") (pinfunction "A_A") (pintype "passive"))
    )
    (net (code "31") (name "3V3_INPUT1") (class "Default")
      (node (ref "C45") (pin "1") (pinfunction "1_1") (pintype "passive"))
      (node (ref "OPTO1") (pin "4") (pinfunction "CT_4") (pintype "passive"))
      (node (ref "R47") (pin "1") (pinfunction "1_1") (pintype "passive"))
      (node (ref "U3") (pin "35") (pinfunction "IO42_35") (pintype "bidirectional"))
    )
    (net (code "32") (name "3V3_INPUT2") (class "Default")
      (node (ref "C46") (pin "1") (pinfunction "1_1") (pintype "passive"))
      (node (ref "OPTO2") (pin "4") (pinfunction "CT_4") (pintype "passive"))
      (node (ref "R46") (pin "1") (pinfunction "1_1") (pintype "passive"))
      (node (ref "U3") (pin "34") (pinfunction "IO41_34") (pintype "bidirectional"))
    )
    (net (code "33") (name "3V3_INPUT3") (class "Default")
      (node (ref "C47") (pin "1") (pinfunction "1_1") (pintype "passive"))
      (node (ref "OPTO3") (pin "4") (pinfunction "CT_4") (pintype "passive"))
      (node (ref "R42") (pin "1") (pinfunction "1_1") (pintype "passive"))
      (node (ref "U3") (pin "33") (pinfunction "IO40_33") (pintype "bidirectional"))
    )
    (net (code "34") (name "3V3_INPUT4") (class "Default")
      (node (ref "C6") (pin "1") (pinfunction "1_1") (pintype "passive"))
      (node (ref "OPTO4") (pin "4") (pinfunction "CT_4") (pintype "passive"))
      (node (ref "R15") (pin "1") (pinfunction "1_1") (pintype "passive"))
      (node (ref "U3") (pin "5") (pinfunction "IO5_5") (pintype "bidirectional"))
    )
    (net (code "35") (name "3V3_INPUT5") (class "Default")
      (node (ref "C9") (pin "1") (pinfunction "1_1") (pintype "passive"))
      (node (ref "OPTO5") (pin "4") (pinfunction "CT_4") (pintype "passive"))
      (node (ref "R14") (pin "1") (pinfunction "1_1") (pintype "passive"))
      (node (ref "U3") (pin "6") (pinfunction "IO6_6") (pintype "bidirectional"))
    )
    (net (code "36") (name "3V3_INPUT6") (class "Default")
      (node (ref "C10") (pin "1") (pinfunction "1_1") (pintype "passive"))
      (node (ref "OPTO6") (pin "4") (pinfunction "CT_4") (pintype "passive"))
      (node (ref "R13") (pin "1") (pinfunction "1_1") (pintype "passive"))
      (node (ref "U3") (pin "7") (pinfunction "IO7_7") (pintype "bidirectional"))
    )
    (net (code "37") (name "3V3_INPUT7") (class "Default")
      (node (ref "C11") (pin "1") (pinfunction "1_1") (pintype "passive"))
      (node (ref "OPTO7") (pin "4") (pinfunction "CT_4") (pintype "passive"))
      (node (ref "R26") (pin "1") (pinfunction "1_1") (pintype "passive"))
      (node (ref "U3") (pin "8") (pinfunction "IO15_8") (pintype "bidirectional"))
    )
    (net (code "38") (name "3V3_INPUT8") (class "Default")
      (node (ref "C12") (pin "1") (pinfunction "1_1") (pintype "passive"))
      (node (ref "OPTO8") (pin "4") (pinfunction "CT_4") (pintype "passive"))
      (node (ref "R25") (pin "1") (pinfunction "1_1") (pintype "passive"))
      (node (ref "U3") (pin "9") (pinfunction "IO16_9") (pintype "bidirectional"))
    )
    (net (code "39") (name "5V") (class "Default")
      (node (ref "C16") (pin "1") (pinfunction "1_1") (pintype "passive"))
      (node (ref "C8") (pin "2") (pinfunction "2_2") (pintype "passive"))
      (node (ref "D13") (pin "C") (pinfunction "C_C") (pintype "passive"))
      (node (ref "D14") (pin "C") (pinfunction "C_C") (pintype "passive"))
      (node (ref "D31") (pin "C") (pinfunction "C_C") (pintype "passive"))
      (node (ref "D33") (pin "C") (pinfunction "C_C") (pintype "passive"))
      (node (ref "IC5") (pin "3") (pinfunction "IN_3") (pintype "input"))
      (node (ref "NEOPIXEL1") (pin "2A") (pinfunction "P$2_2A") (pintype "bidirectional"))
      (node (ref "NEOPIXEL1") (pin "2B") (pinfunction "P$2_2B") (pintype "bidirectional"))
      (node (ref "R10") (pin "2") (pinfunction "2_2") (pintype "passive"))
      (node (ref "R11") (pin "2") (pinfunction "2_2") (pintype "passive"))
      (node (ref "R12") (pin "2") (pinfunction "2_2") (pintype "passive"))
      (node (ref "R18") (pin "1") (pinfunction "1_1") (pintype "passive"))
      (node (ref "R19") (pin "1") (pinfunction "1_1") (pintype "passive"))
      (node (ref "R21") (pin "2") (pinfunction "2_2") (pintype "passive"))
      (node (ref "R23") (pin "2") (pinfunction "2_2") (pintype "passive"))
      (node (ref "R31") (pin "1") (pinfunction "1_1") (pintype "passive"))
      (node (ref "R32") (pin "1") (pinfunction "1_1") (pintype "passive"))
      (node (ref "R33") (pin "1") (pinfunction "1_1") (pintype "passive"))
      (node (ref "R43") (pin "2") (pinfunction "2_2") (pintype "passive"))
      (node (ref "R44") (pin "2") (pinfunction "2_2") (pintype "passive"))
      (node (ref "R45") (pin "2") (pinfunction "2_2") (pintype "passive"))
      (node (ref "R6") (pin "1") (pinfunction "1_1") (pintype "passive"))
      (node (ref "R8") (pin "1") (pinfunction "1_1") (pintype "passive"))
      (node (ref "R9") (pin "1") (pinfunction "1_1") (pintype "passive"))
      (node (ref "U$1") (pin "COIL-") (pinfunction "COIL-_COIL-") (pintype "bidirectional"))
      (node (ref "U$3") (pin "COIL-") (pinfunction "COIL-_COIL-") (pintype "bidirectional"))
    )
    (net (code "40") (name "GND") (class "Default")
      (node (ref "C10") (pin "2") (pinfunction "2_2") (pintype "passive"))
      (node (ref "C11") (pin "2") (pinfunction "2_2") (pintype "passive"))
      (node (ref "C12") (pin "2") (pinfunction "2_2") (pintype "passive"))
      (node (ref "C14") (pin "2") (pinfunction "2_2") (pintype "passive"))
      (node (ref "C15") (pin "2") (pinfunction "2_2") (pintype "passive"))
      (node (ref "C16") (pin "2") (pinfunction "2_2") (pintype "passive"))
      (node (ref "C17") (pin "2") (pinfunction "2_2") (pintype "passive"))
      (node (ref "C19") (pin "2") (pinfunction "2_2") (pintype "passive"))
      (node (ref "C20") (pin "1") (pinfunction "1_1") (pintype "passive"))
      (node (ref "C21") (pin "1") (pinfunction "1_1") (pintype "passive"))
      (node (ref "C22") (pin "2") (pinfunction "2_2") (pintype "passive"))
      (node (ref "C23") (pin "-") (pinfunction "-_-") (pintype "passive"))
      (node (ref "C24") (pin "-") (pinfunction "-_-") (pintype "passive"))
      (node (ref "C45") (pin "2") (pinfunction "2_2") (pintype "passive"))
      (node (ref "C47") (pin "2") (pinfunction "2_2") (pintype "passive"))
      (node (ref "C6") (pin "2") (pinfunction "2_2") (pintype "passive"))
      (node (ref "C8") (pin "1") (pinfunction "1_1") (pintype "passive"))
      (node (ref "C9") (pin "2") (pinfunction "2_2") (pintype "passive"))
      (node (ref "CON3") (pin "GND") (pinfunction "GND_GND") (pintype "bidirectional"))
      (node (ref "CON3") (pin "GND2") (pinfunction "GND_GND2") (pintype "bidirectional"))
      (node (ref "D15") (pin "A") (pinfunction "A_A") (pintype "passive"))
      (node (ref "D28") (pin "A") (pinfunction "A_A") (pintype "passive"))
      (node (ref "D7") (pin "A") (pinfunction "A_A") (pintype "passive"))
      (node (ref "IC4") (pin "3") (pinfunction "GND_3") (pintype "power_in"))
      (node (ref "IC4") (pin "5") (pinfunction "EN_5") (pintype "input"))
      (node (ref "IC4") (pin "6") (pinfunction "GND_6") (pintype "power_in"))
      (node (ref "IC5") (pin "1") (pinfunction "ADJ_1") (pintype "input"))
      (node (ref "IN1_2") (pin "2A") (pinfunction "P$2_2A") (pintype "bidirectional"))
      (node (ref "IN1_2") (pin "2B") (pinfunction "P$2_2B") (pintype "bidirectional"))
      (node (ref "IN1_2") (pin "4A") (pinfunction "P$4_4A") (pintype "bidirectional"))
      (node (ref "IN1_2") (pin "4B") (pinfunction "P$4_4B") (pintype "bidirectional"))
      (node (ref "IN3_4") (pin "2A") (pinfunction "P$2_2A") (pintype "bidirectional"))
      (node (ref "IN3_4") (pin "2B") (pinfunction "P$2_2B") (pintype "bidirectional"))
      (node (ref "IN3_4") (pin "4A") (pinfunction "P$4_4A") (pintype "bidirectional"))
      (node (ref "IN3_4") (pin "4B") (pinfunction "P$4_4B") (pintype "bidirectional"))
      (node (ref "IN5_6") (pin "2A") (pinfunction "P$2_2A") (pintype "bidirectional"))
      (node (ref "IN5_6") (pin "2B") (pinfunction "P$2_2B") (pintype "bidirectional"))
      (node (ref "IN5_6") (pin "4A") (pinfunction "P$4_4A") (pintype "bidirectional"))
      (node (ref "IN5_6") (pin "4B") (pinfunction "P$4_4B") (pintype "bidirectional"))
      (node (ref "IN7_8") (pin "2A") (pinfunction "P$2_2A") (pintype "bidirectional"))
      (node (ref "IN7_8") (pin "2B") (pinfunction "P$2_2B") (pintype "bidirectional"))
      (node (ref "IN7_8") (pin "4A") (pinfunction "P$4_4A") (pintype "bidirectional"))
      (node (ref "IN7_8") (pin "4B") (pinfunction "P$4_4B") (pintype "bidirectional"))
      (node (ref "MODE") (pin "1") (pinfunction "1_1") (pintype "passive"))
      (node (ref "NEOPIXEL1") (pin "3A") (pinfunction "P$3_3A") (pintype "bidirectional"))
      (node (ref "NEOPIXEL1") (pin "3B") (pinfunction "P$3_3B") (pintype "bidirectional"))
      (node (ref "OPTO1") (pin "3") (pinfunction "ET_3") (pintype "passive"))
      (node (ref "OPTO2") (pin "3") (pinfunction "ET_3") (pintype "passive"))
      (node (ref "OPTO3") (pin "3") (pinfunction "ET_3") (pintype "passive"))
      (node (ref "OPTO4") (pin "3") (pinfunction "ET_3") (pintype "passive"))
      (node (ref "OPTO5") (pin "3") (pinfunction "ET_3") (pintype "passive"))
      (node (ref "OPTO6") (pin "3") (pinfunction "ET_3") (pintype "passive"))
      (node (ref "OPTO7") (pin "3") (pinfunction "ET_3") (pintype "passive"))
      (node (ref "OPTO8") (pin "3") (pinfunction "ET_3") (pintype "passive"))
      (node (ref "Q10") (pin "3") (pinfunction "S_3") (pintype "passive"))
      (node (ref "Q11") (pin "3") (pinfunction "S_3") (pintype "passive"))
      (node (ref "Q12") (pin "3") (pinfunction "S_3") (pintype "passive"))
      (node (ref "Q14") (pin "E") (pinfunction "E_E") (pintype "passive"))
      (node (ref "Q34") (pin "E") (pinfunction "E_E") (pintype "passive"))
      (node (ref "Q5") (pin "3") (pinfunction "S_3") (pintype "passive"))
      (node (ref "Q6") (pin "3") (pinfunction "S_3") (pintype "passive"))
      (node (ref "Q7") (pin "3") (pinfunction "S_3") (pintype "passive"))
      (node (ref "Q8") (pin "3") (pinfunction "S_3") (pintype "passive"))
      (node (ref "Q9") (pin "3") (pinfunction "S_3") (pintype "passive"))
      (node (ref "R155") (pin "2") (pinfunction "2_2") (pintype "passive"))
      (node (ref "R28") (pin "1") (pinfunction "1_1") (pintype "passive"))
      (node (ref "R30") (pin "1") (pinfunction "1_1") (pintype "passive"))
      (node (ref "R35") (pin "1") (pinfunction "1_1") (pintype "passive"))
      (node (ref "R37") (pin "1") (pinfunction "1_1") (pintype "passive"))
      (node (ref "R39") (pin "1") (pinfunction "1_1") (pintype "passive"))
      (node (ref "R41") (pin "1") (pinfunction "1_1") (pintype "passive"))
      (node (ref "R49") (pin "1") (pinfunction "1_1") (pintype "passive"))
      (node (ref "R5") (pin "1") (pinfunction "1_1") (pintype "passive"))
      (node (ref "R55") (pin "2") (pinfunction "2_2") (pintype "passive"))
      (node (ref "R63") (pin "1") (pinfunction "1_1") (pintype "passive"))
      (node (ref "R7") (pin "1") (pinfunction "1_1") (pintype "passive"))
      (node (ref "RESET") (pin "1") (pinfunction "1_1") (pintype "passive"))
      (node (ref "S1") (pin "1") (pinfunction "1_1") (pintype "passive"))
      (node (ref "S2") (pin "1") (pinfunction "1_1") (pintype "passive"))
      (node (ref "S3") (pin "1") (pinfunction "1_1") (pintype "passive"))
      (node (ref "S4") (pin "1") (pinfunction "1_1") (pintype "passive"))
      (node (ref "S5") (pin "1") (pinfunction "1_1") (pintype "passive"))
      (node (ref "S6") (pin "1") (pinfunction "1_1") (pintype "passive"))
      (node (ref "S7") (pin "1") (pinfunction "1_1") (pintype "passive"))
      (node (ref "S8") (pin "1") (pinfunction "1_1") (pintype "passive"))
      (node (ref "U3") (pin "1") (pinfunction "GND_1") (pintype "power_in"))
      (node (ref "U3") (pin "40") (pinfunction "GND_40") (pintype "power_in"))
      (node (ref "U3") (pin "41_1") (pinfunction "GND_41_1") (pintype "power_in"))
      (node (ref "U3") (pin "41_2") (pinfunction "GND_41_2") (pintype "power_in"))
      (node (ref "U3") (pin "41_3") (pinfunction "GND_41_3") (pintype "power_in"))
      (node (ref "U3") (pin "41_4") (pinfunction "GND_41_4") (pintype "power_in"))
      (node (ref "U3") (pin "41_5") (pinfunction "GND_41_5") (pintype "power_in"))
      (node (ref "U3") (pin "41_6") (pinfunction "GND_41_6") (pintype "power_in"))
      (node (ref "U3") (pin "41_7") (pinfunction "GND_41_7") (pintype "power_in"))
      (node (ref "U3") (pin "41_8") (pinfunction "GND_41_8") (pintype "power_in"))
      (node (ref "U3") (pin "41_9") (pinfunction "GND_41_9") (pintype "power_in"))
      (node (ref "VIN") (pin "2A") (pinfunction "P$2_2A") (pintype "bidirectional"))
      (node (ref "VIN") (pin "2B") (pinfunction "P$2_2B") (pintype "bidirectional"))
    )
    (net (code "41") (name "INPUT1") (class "Default")
      (node (ref "DI1") (pin "C") (pinfunction "C_C") (pintype "passive"))
      (node (ref "IN1_2") (pin "1A") (pinfunction "P$1_1A") (pintype "bidirectional"))
      (node (ref "IN1_2") (pin "1B") (pinfunction "P$1_1B") (pintype "bidirectional"))
      (node (ref "S1") (pin "3") (pinfunction "2_3") (pintype "passive"))
    )
    (net (code "42") (name "INPUT2") (class "Default")
      (node (ref "DI2") (pin "C") (pinfunction "C_C") (pintype "passive"))
      (node (ref "IN1_2") (pin "3A") (pinfunction "P$3_3A") (pintype "bidirectional"))
      (node (ref "IN1_2") (pin "3B") (pinfunction "P$3_3B") (pintype "bidirectional"))
      (node (ref "S2") (pin "3") (pinfunction "2_3") (pintype "passive"))
    )
    (net (code "43") (name "INPUT3") (class "Default")
      (node (ref "DI3") (pin "C") (pinfunction "C_C") (pintype "passive"))
      (node (ref "IN3_4") (pin "1A") (pinfunction "P$1_1A") (pintype "bidirectional"))
      (node (ref "IN3_4") (pin "1B") (pinfunction "P$1_1B") (pintype "bidirectional"))
      (node (ref "S3") (pin "3") (pinfunction "2_3") (pintype "passive"))
    )
    (net (code "44") (name "INPUT4") (class "Default")
      (node (ref "DI4") (pin "C") (pinfunction "C_C") (pintype "passive"))
      (node (ref "IN3_4") (pin "3A") (pinfunction "P$3_3A") (pintype "bidirectional"))
      (node (ref "IN3_4") (pin "3B") (pinfunction "P$3_3B") (pintype "bidirectional"))
      (node (ref "S4") (pin "3") (pinfunction "2_3") (pintype "passive"))
    )
    (net (code "45") (name "INPUT5") (class "Default")
      (node (ref "DI5") (pin "C") (pinfunction "C_C") (pintype "passive"))
      (node (ref "IN5_6") (pin "1A") (pinfunction "P$1_1A") (pintype "bidirectional"))
      (node (ref "IN5_6") (pin "1B") (pinfunction "P$1_1B") (pintype "bidirectional"))
      (node (ref "S5") (pin "3") (pinfunction "2_3") (pintype "passive"))
    )
    (net (code "46") (name "INPUT6") (class "Default")
      (node (ref "DI6") (pin "C") (pinfunction "C_C") (pintype "passive"))
      (node (ref "IN5_6") (pin "3A") (pinfunction "P$3_3A") (pintype "bidirectional"))
      (node (ref "IN5_6") (pin "3B") (pinfunction "P$3_3B") (pintype "bidirectional"))
      (node (ref "S6") (pin "3") (pinfunction "2_3") (pintype "passive"))
    )
    (net (code "47") (name "INPUT7") (class "Default")
      (node (ref "DI7") (pin "C") (pinfunction "C_C") (pintype "passive"))
      (node (ref "IN7_8") (pin "1A") (pinfunction "P$1_1A") (pintype "bidirectional"))
      (node (ref "IN7_8") (pin "1B") (pinfunction "P$1_1B") (pintype "bidirectional"))
      (node (ref "S7") (pin "3") (pinfunction "2_3") (pintype "passive"))
    )
    (net (code "48") (name "INPUT8") (class "Default")
      (node (ref "DI8") (pin "C") (pinfunction "C_C") (pintype "passive"))
      (node (ref "IN7_8") (pin "3A") (pinfunction "P$3_3A") (pintype "bidirectional"))
      (node (ref "IN7_8") (pin "3B") (pinfunction "P$3_3B") (pintype "bidirectional"))
      (node (ref "S8") (pin "3") (pinfunction "2_3") (pintype "passive"))
    )
    (net (code "49") (name "MOSFET1-GND") (class "Default")
      (node (ref "D16") (pin "A") (pinfunction "A_A") (pintype "passive"))
      (node (ref "OUT1_2") (pin "4A") (pinfunction "P$4_4A") (pintype "bidirectional"))
      (node (ref "OUT1_2") (pin "4B") (pinfunction "P$4_4B") (pintype "bidirectional"))
      (node (ref "Q5") (pin "4") (pinfunction "D_4") (pintype "passive"))
    )
    (net (code "50") (name "MOSFET1-SIG") (class "Default")
      (node (ref "R62") (pin "1") (pinfunction "1_1") (pintype "passive"))
      (node (ref "U3") (pin "12") (pinfunction "IO8_12") (pintype "bidirectional"))
    )
    (net (code "51") (name "MOSFET2-GND") (class "Default")
      (node (ref "D10") (pin "A") (pinfunction "A_A") (pintype "passive"))
      (node (ref "OUT1_2") (pin "2A") (pinfunction "P$2_2A") (pintype "bidirectional"))
      (node (ref "OUT1_2") (pin "2B") (pinfunction "P$2_2B") (pintype "bidirectional"))
      (node (ref "Q6") (pin "4") (pinfunction "D_4") (pintype "passive"))
    )
    (net (code "52") (name "MOSFET2-SIG") (class "Default")
      (node (ref "R27") (pin "1") (pinfunction "1_1") (pintype "passive"))
      (node (ref "U3") (pin "17") (pinfunction "IO9_17") (pintype "bidirectional"))
    )
    (net (code "53") (name "MOSFET3-GND") (class "Default")
      (node (ref "D11") (pin "A") (pinfunction "A_A") (pintype "passive"))
      (node (ref "OUT3_4") (pin "4A") (pinfunction "P$4_4A") (pintype "bidirectional"))
      (node (ref "OUT3_4") (pin "4B") (pinfunction "P$4_4B") (pintype "bidirectional"))
      (node (ref "Q7") (pin "4") (pinfunction "D_4") (pintype "passive"))
    )
    (net (code "54") (name "MOSFET3-SIG") (class "Default")
      (node (ref "R29") (pin "1") (pinfunction "1_1") (pintype "passive"))
      (node (ref "U3") (pin "18") (pinfunction "IO10_18") (pintype "bidirectional"))
    )
    (net (code "55") (name "MOSFET4-GND") (class "Default")
      (node (ref "D12") (pin "A") (pinfunction "A_A") (pintype "passive"))
      (node (ref "OUT3_4") (pin "2A") (pinfunction "P$2_2A") (pintype "bidirectional"))
      (node (ref "OUT3_4") (pin "2B") (pinfunction "P$2_2B") (pintype "bidirectional"))
      (node (ref "Q8") (pin "4") (pinfunction "D_4") (pintype "passive"))
    )
    (net (code "56") (name "MOSFET4-SIG") (class "Default")
      (node (ref "R34") (pin "1") (pinfunction "1_1") (pintype "passive"))
      (node (ref "U3") (pin "19") (pinfunction "IO11_19") (pintype "bidirectional"))
    )
    (net (code "57") (name "MOSFET5-GND") (class "Default")
      (node (ref "D17") (pin "A") (pinfunction "A_A") (pintype "passive"))
      (node (ref "OUT5_6") (pin "4A") (pinfunction "P$4_4A") (pintype "bidirectional"))
      (node (ref "OUT5_6") (pin "4B") (pinfunction "P$4_4B") (pintype "bidirectional"))
      (node (ref "Q9") (pin "4") (pinfunction "D_4") (pintype "passive"))
    )
    (net (code "58") (name "MOSFET5-SIG") (class "Default")
      (node (ref "R36") (pin "1") (pinfunction "1_1") (pintype "passive"))
      (node (ref "U3") (pin "20") (pinfunction "IO12_20") (pintype "bidirectional"))
    )
    (net (code "59") (name "MOSFET6-GND") (class "Default")
      (node (ref "D18") (pin "A") (pinfunction "A_A") (pintype "passive"))
      (node (ref "OUT5_6") (pin "2A") (pinfunction "P$2_2A") (pintype "bidirectional"))
      (node (ref "OUT5_6") (pin "2B") (pinfunction "P$2_2B") (pintype "bidirectional"))
      (node (ref "Q10") (pin "4") (pinfunction "D_4") (pintype "passive"))
    )
    (net (code "60") (name "MOSFET6-SIG") (class "Default")
      (node (ref "R38") (pin "1") (pinfunction "1_1") (pintype "passive"))
      (node (ref "U3") (pin "21") (pinfunction "IO13_21") (pintype "bidirectional"))
    )
    (net (code "61") (name "MOSFET7-GND") (class "Default")
      (node (ref "D19") (pin "A") (pinfunction "A_A") (pintype "passive"))
      (node (ref "OUT7_8") (pin "4A") (pinfunction "P$4_4A") (pintype "bidirectional"))
      (node (ref "OUT7_8") (pin "4B") (pinfunction "P$4_4B") (pintype "bidirectional"))
      (node (ref "Q11") (pin "4") (pinfunction "D_4") (pintype "passive"))
    )
    (net (code "62") (name "MOSFET7-SIG") (class "Default")
      (node (ref "R40") (pin "1") (pinfunction "1_1") (pintype "passive"))
      (node (ref "U3") (pin "22") (pinfunction "IO14_22") (pintype "bidirectional"))
    )
    (net (code "63") (name "MOSFET8-GND") (class "Default")
      (node (ref "D20") (pin "A") (pinfunction "A_A") (pintype "passive"))
      (node (ref "OUT7_8") (pin "2A") (pinfunction "P$2_2A") (pintype "bidirectional"))
      (node (ref "OUT7_8") (pin "2B") (pinfunction "P$2_2B") (pintype "bidirectional"))
      (node (ref "Q12") (pin "4") (pinfunction "D_4") (pintype "passive"))
    )
    (net (code "64") (name "MOSFET8-SIG") (class "Default")
      (node (ref "R48") (pin "1") (pinfunction "1_1") (pintype "passive"))
      (node (ref "U3") (pin "23") (pinfunction "IO21_23") (pintype "bidirectional"))
    )
    (net (code "65") (name "Net-(CON3-CC1)") (class "Default")
      (node (ref "CON3") (pin "A5") (pinfunction "CC1_A5") (pintype "bidirectional"))
      (node (ref "R7") (pin "2") (pinfunction "2_2") (pintype "passive"))
    )
    (net (code "66") (name "Net-(CON3-CC2)") (class "Default")
      (node (ref "CON3") (pin "B5") (pinfunction "CC2_B5") (pintype "bidirectional"))
      (node (ref "R5") (pin "2") (pinfunction "2_2") (pintype "passive"))
    )
    (net (code "67") (name "Net-(IC4-OUT)") (class "Default")
      (node (ref "D28") (pin "C") (pinfunction "C_C") (pintype "passive"))
      (node (ref "IC4") (pin "2") (pinfunction "OUT_2") (pintype "output"))
      (node (ref "L5") (pin "1") (pinfunction "1_1") (pintype "passive"))
    )
    (net (code "68") (name "Net-(OPTO1-A)") (class "Default")
      (node (ref "OPTO1") (pin "1") (pinfunction "A_1") (pintype "passive"))
      (node (ref "R33") (pin "2") (pinfunction "2_2") (pintype "passive"))
    )
    (net (code "69") (name "Net-(OPTO1-C)") (class "Default")
      (node (ref "DI1") (pin "A") (pinfunction "A_A") (pintype "passive"))
      (node (ref "OPTO1") (pin "2") (pinfunction "C_2") (pintype "passive"))
      (node (ref "R45") (pin "1") (pinfunction "1_1") (pintype "passive"))
    )
    (net (code "70") (name "Net-(OPTO2-A)") (class "Default")
      (node (ref "OPTO2") (pin "1") (pinfunction "A_1") (pintype "passive"))
      (node (ref "R32") (pin "2") (pinfunction "2_2") (pintype "passive"))
    )
    (net (code "71") (name "Net-(OPTO2-C)") (class "Default")
      (node (ref "DI2") (pin "A") (pinfunction "A_A") (pintype "passive"))
      (node (ref "OPTO2") (pin "2") (pinfunction "C_2") (pintype "passive"))
      (node (ref "R44") (pin "1") (pinfunction "1_1") (pintype "passive"))
    )
    (net (code "72") (name "Net-(OPTO3-A)") (class "Default")
      (node (ref "OPTO3") (pin "1") (pinfunction "A_1") (pintype "passive"))
      (node (ref "R31") (pin "2") (pinfunction "2_2") (pintype "passive"))
    )
    (net (code "73") (name "Net-(OPTO3-C)") (class "Default")
      (node (ref "DI3") (pin "A") (pinfunction "A_A") (pintype "passive"))
      (node (ref "OPTO3") (pin "2") (pinfunction "C_2") (pintype "passive"))
      (node (ref "R43") (pin "1") (pinfunction "1_1") (pintype "passive"))
    )
    (net (code "74") (name "Net-(OPTO4-A)") (class "Default")
      (node (ref "OPTO4") (pin "1") (pinfunction "A_1") (pintype "passive"))
      (node (ref "R9") (pin "2") (pinfunction "2_2") (pintype "passive"))
    )
    (net (code "75") (name "Net-(OPTO4-C)") (class "Default")
      (node (ref "DI4") (pin "A") (pinfunction "A_A") (pintype "passive"))
      (node (ref "OPTO4") (pin "2") (pinfunction "C_2") (pintype "passive"))
      (node (ref "R12") (pin "1") (pinfunction "1_1") (pintype "passive"))
    )
    (net (code "76") (name "Net-(OPTO5-A)") (class "Default")
      (node (ref "OPTO5") (pin "1") (pinfunction "A_1") (pintype "passive"))
      (node (ref "R8") (pin "2") (pinfunction "2_2") (pintype "passive"))
    )
    (net (code "77") (name "Net-(OPTO5-C)") (class "Default")
      (node (ref "DI5") (pin "A") (pinfunction "A_A") (pintype "passive"))
      (node (ref "OPTO5") (pin "2") (pinfunction "C_2") (pintype "passive"))
      (node (ref "R11") (pin "1") (pinfunction "1_1") (pintype "passive"))
    )
    (net (code "78") (name "Net-(OPTO6-A)") (class "Default")
      (node (ref "OPTO6") (pin "1") (pinfunction "A_1") (pintype "passive"))
      (node (ref "R6") (pin "2") (pinfunction "2_2") (pintype "passive"))
    )
    (net (code "79") (name "Net-(OPTO6-C)") (class "Default")
      (node (ref "DI6") (pin "A") (pinfunction "A_A") (pintype "passive"))
      (node (ref "OPTO6") (pin "2") (pinfunction "C_2") (pintype "passive"))
      (node (ref "R10") (pin "1") (pinfunction "1_1") (pintype "passive"))
    )
    (net (code "80") (name "Net-(OPTO7-A)") (class "Default")
      (node (ref "OPTO7") (pin "1") (pinfunction "A_1") (pintype "passive"))
      (node (ref "R19") (pin "2") (pinfunction "2_2") (pintype "passive"))
    )
    (net (code "81") (name "Net-(OPTO7-C)") (class "Default")
      (node (ref "DI7") (pin "A") (pinfunction "A_A") (pintype "passive"))
      (node (ref "OPTO7") (pin "2") (pinfunction "C_2") (pintype "passive"))
      (node (ref "R23") (pin "1") (pinfunction "1_1") (pintype "passive"))
    )
    (net (code "82") (name "Net-(OPTO8-A)") (class "Default")
      (node (ref "OPTO8") (pin "1") (pinfunction "A_1") (pintype "passive"))
      (node (ref "R18") (pin "2") (pinfunction "2_2") (pintype "passive"))
    )
    (net (code "83") (name "Net-(OPTO8-C)") (class "Default")
      (node (ref "DI8") (pin "A") (pinfunction "A_A") (pintype "passive"))
      (node (ref "OPTO8") (pin "2") (pinfunction "C_2") (pintype "passive"))
      (node (ref "R21") (pin "1") (pinfunction "1_1") (pintype "passive"))
    )
    (net (code "84") (name "Net-(Q5-G)") (class "Default")
      (node (ref "Q5") (pin "1") (pinfunction "G_1") (pintype "passive"))
      (node (ref "R62") (pin "2") (pinfunction "2_2") (pintype "passive"))
      (node (ref "R63") (pin "2") (pinfunction "2_2") (pintype "passive"))
    )
    (net (code "85") (name "Net-(Q6-G)") (class "Default")
      (node (ref "Q6") (pin "1") (pinfunction "G_1") (pintype "passive"))
      (node (ref "R27") (pin "2") (pinfunction "2_2") (pintype "passive"))
      (node (ref "R28") (pin "2") (pinfunction "2_2") (pintype "passive"))
    )
    (net (code "86") (name "Net-(Q7-G)") (class "Default")
      (node (ref "Q7") (pin "1") (pinfunction "G_1") (pintype "passive"))
      (node (ref "R29") (pin "2") (pinfunction "2_2") (pintype "passive"))
      (node (ref "R30") (pin "2") (pinfunction "2_2") (pintype "passive"))
    )
    (net (code "87") (name "Net-(Q8-G)") (class "Default")
      (node (ref "Q8") (pin "1") (pinfunction "G_1") (pintype "passive"))
      (node (ref "R34") (pin "2") (pinfunction "2_2") (pintype "passive"))
      (node (ref "R35") (pin "2") (pinfunction "2_2") (pintype "passive"))
    )
    (net (code "88") (name "Net-(Q9-G)") (class "Default")
      (node (ref "Q9") (pin "1") (pinfunction "G_1") (pintype "passive"))
      (node (ref "R36") (pin "2") (pinfunction "2_2") (pintype "passive"))
      (node (ref "R37") (pin "2") (pinfunction "2_2") (pintype "passive"))
    )
    (net (code "89") (name "Net-(Q10-G)") (class "Default")
      (node (ref "Q10") (pin "1") (pinfunction "G_1") (pintype "passive"))
      (node (ref "R38") (pin "2") (pinfunction "2_2") (pintype "passive"))
      (node (ref "R39") (pin "2") (pinfunction "2_2") (pintype "passive"))
    )
    (net (code "90") (name "Net-(Q11-G)") (class "Default")
      (node (ref "Q11") (pin "1") (pinfunction "G_1") (pintype "passive"))
      (node (ref "R40") (pin "2") (pinfunction "2_2") (pintype "passive"))
      (node (ref "R41") (pin "2") (pinfunction "2_2") (pintype "passive"))
    )
    (net (code "91") (name "Net-(Q12-G)") (class "Default")
      (node (ref "Q12") (pin "1") (pinfunction "G_1") (pintype "passive"))
      (node (ref "R48") (pin "2") (pinfunction "2_2") (pintype "passive"))
      (node (ref "R49") (pin "2") (pinfunction "2_2") (pintype "passive"))
    )
    (net (code "92") (name "Net-(Q14-PadB)") (class "Default")
      (node (ref "Q14") (pin "B") (pinfunction "B_B") (pintype "passive"))
      (node (ref "R54") (pin "1") (pinfunction "1_1") (pintype "passive"))
      (node (ref "R55") (pin "1") (pinfunction "1_1") (pintype "passive"))
    )
    (net (code "93") (name "Net-(Q34-PadB)") (class "Default")
      (node (ref "Q34") (pin "B") (pinfunction "B_B") (pintype "passive"))
      (node (ref "R154") (pin "1") (pinfunction "1_1") (pintype "passive"))
      (node (ref "R155") (pin "1") (pinfunction "1_1") (pintype "passive"))
    )
    (net (code "94") (name "Net-(U$1-COIL=)") (class "Default")
      (node (ref "D33") (pin "A") (pinfunction "A_A") (pintype "passive"))
      (node (ref "Q14") (pin "C") (pinfunction "C_C") (pintype "passive"))
      (node (ref "U$1") (pin "COIL+") (pinfunction "COIL=_COIL+") (pintype "bidirectional"))
    )
    (net (code "95") (name "Net-(U$3-COIL=)") (class "Default")
      (node (ref "D31") (pin "A") (pinfunction "A_A") (pintype "passive"))
      (node (ref "Q34") (pin "C") (pinfunction "C_C") (pintype "passive"))
      (node (ref "U$3") (pin "COIL+") (pinfunction "COIL=_COIL+") (pintype "bidirectional"))
    )
    (net (code "96") (name "RESET") (class "Default")
      (node (ref "C14") (pin "1") (pinfunction "1_1") (pintype "passive"))
      (node (ref "R16") (pin "1") (pinfunction "1_1") (pintype "passive"))
      (node (ref "RESET") (pin "3") (pinfunction "2_3") (pintype "passive"))
      (node (ref "U3") (pin "3") (pinfunction "EN_3") (pintype "input"))
    )
    (net (code "97") (name "SHLD") (class "Default")
      (node (ref "CON3") (pin "SHLD1") (pinfunction "SHLD_SHLD1") (pintype "bidirectional"))
      (node (ref "CON3") (pin "SHLD2") (pinfunction "SHLD_SHLD2") (pintype "bidirectional"))
      (node (ref "CON3") (pin "SHLD3") (pinfunction "SHLD_SHLD3") (pintype "bidirectional"))
      (node (ref "CON3") (pin "SHLD4") (pinfunction "SHLD_SHLD4") (pintype "bidirectional"))
      (node (ref "CON3") (pin "SHLD5") (pinfunction "SHLD_SHLD5") (pintype "bidirectional"))
      (node (ref "CON3") (pin "SHLD6") (pinfunction "SHLD_SHLD6") (pintype "bidirectional"))
      (node (ref "CON3") (pin "SHLD7") (pinfunction "SHLD_SHLD7") (pintype "bidirectional"))
      (node (ref "CON3") (pin "SHLD8") (pinfunction "SHLD_SHLD8") (pintype "bidirectional"))
    )
    (net (code "98") (name "unconnected-(C46-Pad2)") (class "Default")
      (node (ref "C46") (pin "2") (pinfunction "2_2") (pintype "passive"))
    )
  )
)
